# Shield_Moteur_DIP.net
KiCad netlist of a schematic drawn in EAGLE
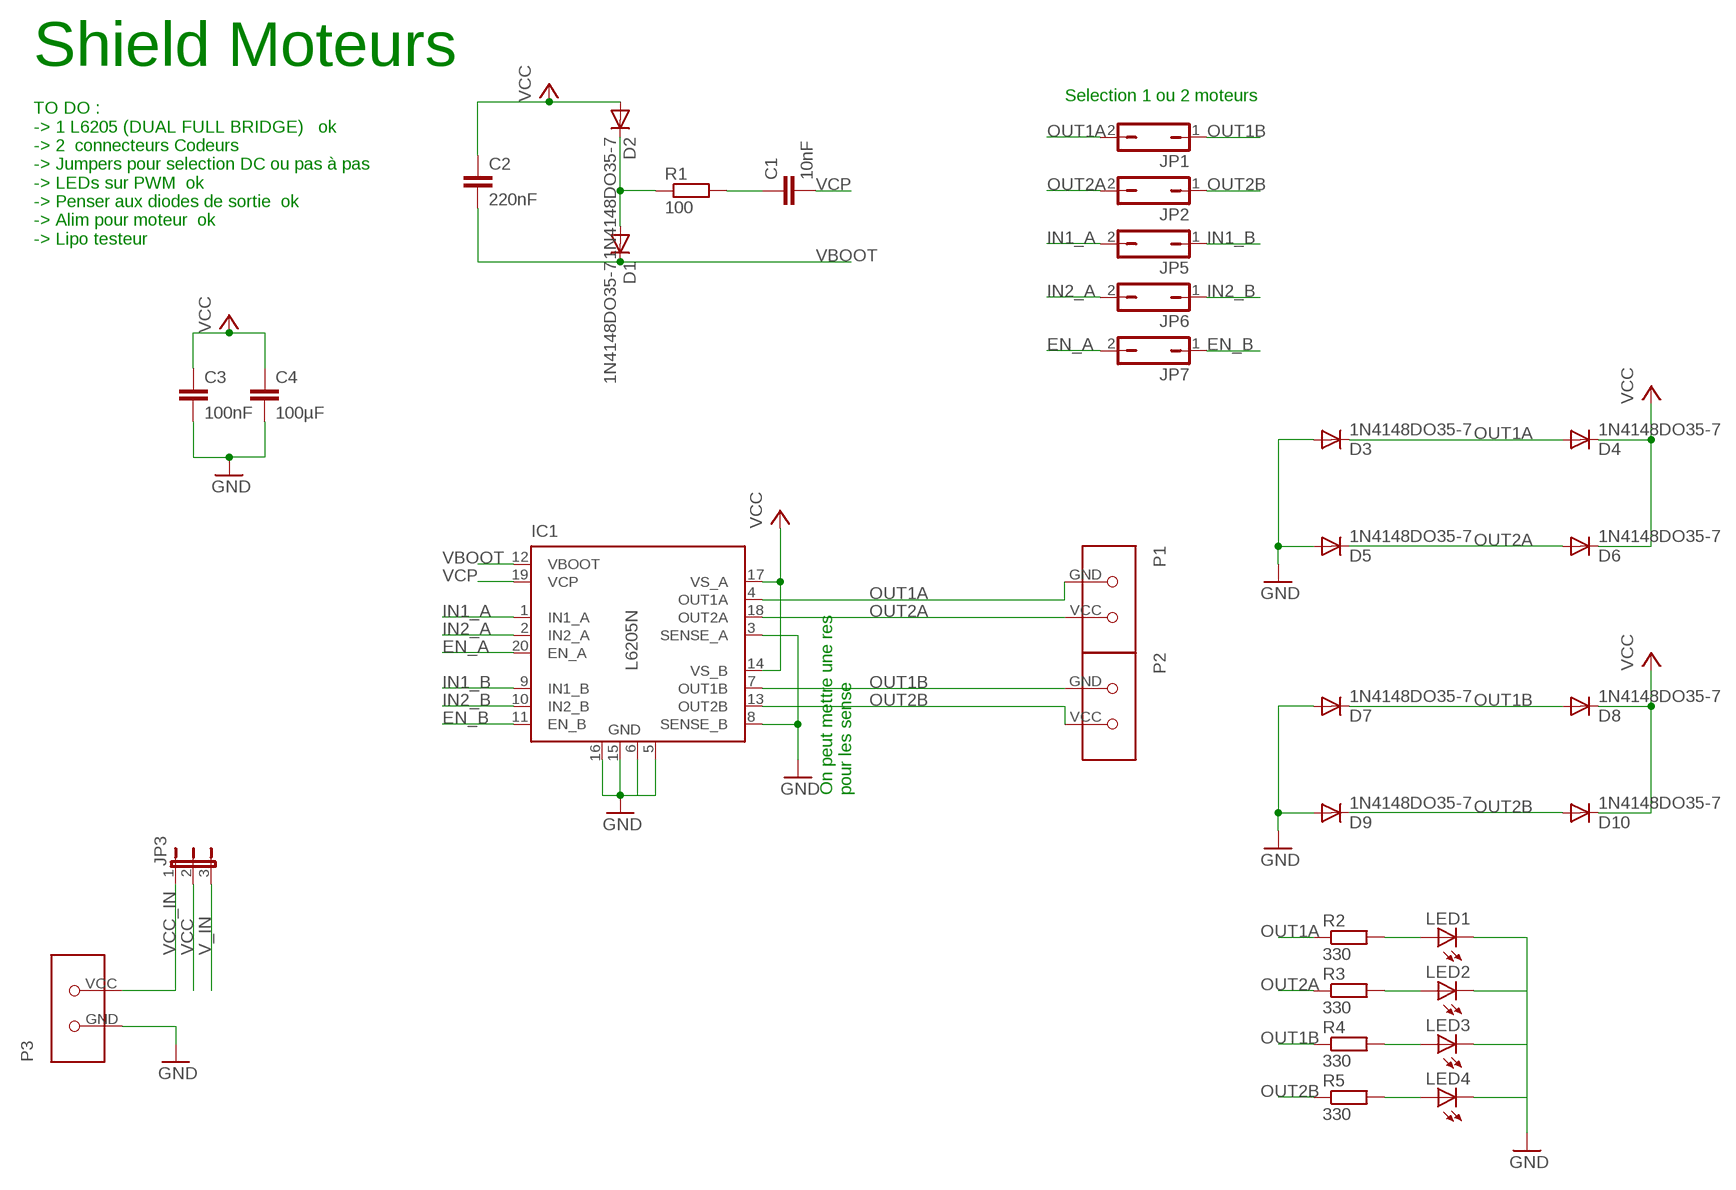
[diagram p0: schematic, sheet 1]

(export (version "E")
  (design (tool "Eeschema 10.0.6"))
  (components
    (comp (ref "C1")
      (value "10nF")
      (footprint "eagle-import:C050-035X075")
      (libsource (lib "eagle-import") (part "C-EU050-035X075"))
    )
    (comp (ref "C2")
      (value "220nF")
      (footprint "eagle-import:C050-035X075")
      (libsource (lib "eagle-import") (part "C-EU050-035X075"))
    )
    (comp (ref "C3")
      (value "100nF")
      (footprint "eagle-import:C050-035X075")
      (libsource (lib "eagle-import") (part "C-EU050-035X075"))
    )
    (comp (ref "C4")
      (value "100µF")
      (footprint "eagle-import:C050-035X075")
      (libsource (lib "eagle-import") (part "C-EU050-035X075"))
    )
    (comp (ref "D1")
      (value "1N4148DO35-7")
      (footprint "eagle-import:DO35-7")
      (libsource (lib "eagle-import") (part "1N4148DO35-7"))
    )
    (comp (ref "D2")
      (value "1N4148DO35-7")
      (footprint "eagle-import:DO35-7")
      (libsource (lib "eagle-import") (part "1N4148DO35-7"))
    )
    (comp (ref "D3")
      (value "1N4148DO35-7")
      (footprint "eagle-import:DO35-7")
      (libsource (lib "eagle-import") (part "1N4148DO35-7"))
    )
    (comp (ref "D4")
      (value "1N4148DO35-7")
      (footprint "eagle-import:DO35-7")
      (libsource (lib "eagle-import") (part "1N4148DO35-7"))
    )
    (comp (ref "D5")
      (value "1N4148DO35-7")
      (footprint "eagle-import:DO35-7")
      (libsource (lib "eagle-import") (part "1N4148DO35-7"))
    )
    (comp (ref "D6")
      (value "1N4148DO35-7")
      (footprint "eagle-import:DO35-7")
      (libsource (lib "eagle-import") (part "1N4148DO35-7"))
    )
    (comp (ref "D7")
      (value "1N4148DO35-7")
      (footprint "eagle-import:DO35-7")
      (libsource (lib "eagle-import") (part "1N4148DO35-7"))
    )
    (comp (ref "D8")
      (value "1N4148DO35-7")
      (footprint "eagle-import:DO35-7")
      (libsource (lib "eagle-import") (part "1N4148DO35-7"))
    )
    (comp (ref "D9")
      (value "1N4148DO35-7")
      (footprint "eagle-import:DO35-7")
      (libsource (lib "eagle-import") (part "1N4148DO35-7"))
    )
    (comp (ref "D10")
      (value "1N4148DO35-7")
      (footprint "eagle-import:DO35-7")
      (libsource (lib "eagle-import") (part "1N4148DO35-7"))
    )
    (comp (ref "IC1")
      (value "L6205N")
      (footprint "eagle-import:DIL20")
      (fields (field (name "MF") "Arrow Electronics"))
      (libsource (lib "eagle-import") (part "L6205N"))
    )
    (comp (ref "JP1")
      (value "JP1Q")
      (footprint "eagle-import:JP1")
      (libsource (lib "eagle-import") (part "JP1Q"))
    )
    (comp (ref "JP2")
      (value "JP1Q")
      (footprint "eagle-import:JP1")
      (libsource (lib "eagle-import") (part "JP1Q"))
    )
    (comp (ref "JP3")
      (value "JP2E")
      (footprint "eagle-import:JP2")
      (libsource (lib "eagle-import") (part "JP2E"))
    )
    (comp (ref "JP5")
      (value "JP1Q")
      (footprint "eagle-import:JP1")
      (libsource (lib "eagle-import") (part "JP1Q"))
    )
    (comp (ref "JP6")
      (value "JP1Q")
      (footprint "eagle-import:JP1")
      (libsource (lib "eagle-import") (part "JP1Q"))
    )
    (comp (ref "JP7")
      (value "JP1Q")
      (footprint "eagle-import:JP1")
      (libsource (lib "eagle-import") (part "JP1Q"))
    )
    (comp (ref "LED1")
      (value "LED3MM")
      (footprint "eagle-import:LED3MM")
      (libsource (lib "eagle-import") (part "LED3MM"))
    )
    (comp (ref "LED2")
      (value "LED3MM")
      (footprint "eagle-import:LED3MM")
      (libsource (lib "eagle-import") (part "LED3MM"))
    )
    (comp (ref "LED3")
      (value "LED3MM")
      (footprint "eagle-import:LED3MM")
      (libsource (lib "eagle-import") (part "LED3MM"))
    )
    (comp (ref "LED4")
      (value "LED3MM")
      (footprint "eagle-import:LED3MM")
      (libsource (lib "eagle-import") (part "LED3MM"))
    )
    (comp (ref "P1")
      (value "BORNIER_3.5MM")
      (footprint "eagle-import:BORNIER_COUDEE_3.5")
      (libsource (lib "eagle-import") (part "BORNIER_3.5MM"))
    )
    (comp (ref "P2")
      (value "BORNIER_3.5MM")
      (footprint "eagle-import:BORNIER_COUDEE_3.5")
      (libsource (lib "eagle-import") (part "BORNIER_3.5MM"))
    )
    (comp (ref "P3")
      (value "BORNIER_3.5MM")
      (footprint "eagle-import:BORNIER_COUDEE_3.5")
      (libsource (lib "eagle-import") (part "BORNIER_3.5MM"))
    )
    (comp (ref "R1")
      (value "100")
      (footprint "eagle-import:0204_7")
      (libsource (lib "eagle-import") (part "R-EU_0204/7"))
    )
    (comp (ref "R2")
      (value "330")
      (footprint "eagle-import:0204_7")
      (libsource (lib "eagle-import") (part "R-EU_0204/7"))
    )
    (comp (ref "R3")
      (value "330")
      (footprint "eagle-import:0204_7")
      (libsource (lib "eagle-import") (part "R-EU_0204/7"))
    )
    (comp (ref "R4")
      (value "330")
      (footprint "eagle-import:0204_7")
      (libsource (lib "eagle-import") (part "R-EU_0204/7"))
    )
    (comp (ref "R5")
      (value "330")
      (footprint "eagle-import:0204_7")
      (libsource (lib "eagle-import") (part "R-EU_0204/7"))
    )
  )
  (nets
    (net (code "1") (name "/EN_A") (class "Default")
      (node (ref "IC1") (pin "20") (pinfunction "EN_A_20") (pintype "input"))
      (node (ref "JP7") (pin "2") (pinfunction "2_2") (pintype "passive"))
    )
    (net (code "2") (name "/EN_B") (class "Default")
      (node (ref "IC1") (pin "11") (pinfunction "EN_B_11") (pintype "input"))
      (node (ref "JP7") (pin "1") (pinfunction "1_1") (pintype "passive"))
    )
    (net (code "3") (name "/IN1_A") (class "Default")
      (node (ref "IC1") (pin "1") (pinfunction "IN1_A_1") (pintype "input"))
      (node (ref "JP5") (pin "2") (pinfunction "2_2") (pintype "passive"))
    )
    (net (code "4") (name "/IN1_B") (class "Default")
      (node (ref "IC1") (pin "9") (pinfunction "IN1_B_9") (pintype "input"))
      (node (ref "JP5") (pin "1") (pinfunction "1_1") (pintype "passive"))
    )
    (net (code "5") (name "/IN2_A") (class "Default")
      (node (ref "IC1") (pin "2") (pinfunction "IN2_A_2") (pintype "input"))
      (node (ref "JP6") (pin "2") (pinfunction "2_2") (pintype "passive"))
    )
    (net (code "6") (name "/IN2_B") (class "Default")
      (node (ref "IC1") (pin "10") (pinfunction "IN2_B_10") (pintype "input"))
      (node (ref "JP6") (pin "1") (pinfunction "1_1") (pintype "passive"))
    )
    (net (code "7") (name "/OUT1A") (class "Default")
      (node (ref "D3") (pin "C") (pinfunction "C_C") (pintype "passive"))
      (node (ref "D4") (pin "A") (pinfunction "A_A") (pintype "passive"))
      (node (ref "IC1") (pin "4") (pinfunction "OUT1A_4") (pintype "output"))
      (node (ref "JP1") (pin "2") (pinfunction "2_2") (pintype "passive"))
      (node (ref "P1") (pin "GND") (pinfunction "GND_GND") (pintype "bidirectional"))
      (node (ref "R2") (pin "1") (pinfunction "1_1") (pintype "passive"))
    )
    (net (code "8") (name "/OUT1B") (class "Default")
      (node (ref "D7") (pin "C") (pinfunction "C_C") (pintype "passive"))
      (node (ref "D8") (pin "A") (pinfunction "A_A") (pintype "passive"))
      (node (ref "IC1") (pin "7") (pinfunction "OUT1B_7") (pintype "output"))
      (node (ref "JP1") (pin "1") (pinfunction "1_1") (pintype "passive"))
      (node (ref "P2") (pin "GND") (pinfunction "GND_GND") (pintype "bidirectional"))
      (node (ref "R4") (pin "1") (pinfunction "1_1") (pintype "passive"))
    )
    (net (code "9") (name "/OUT2A") (class "Default")
      (node (ref "D5") (pin "C") (pinfunction "C_C") (pintype "passive"))
      (node (ref "D6") (pin "A") (pinfunction "A_A") (pintype "passive"))
      (node (ref "IC1") (pin "18") (pinfunction "OUT2A_18") (pintype "output"))
      (node (ref "JP2") (pin "2") (pinfunction "2_2") (pintype "passive"))
      (node (ref "P1") (pin "VCC") (pinfunction "VCC_VCC") (pintype "bidirectional"))
      (node (ref "R3") (pin "1") (pinfunction "1_1") (pintype "passive"))
    )
    (net (code "10") (name "/OUT2B") (class "Default")
      (node (ref "D10") (pin "A") (pinfunction "A_A") (pintype "passive"))
      (node (ref "D9") (pin "C") (pinfunction "C_C") (pintype "passive"))
      (node (ref "IC1") (pin "13") (pinfunction "OUT2B_13") (pintype "output"))
      (node (ref "JP2") (pin "1") (pinfunction "1_1") (pintype "passive"))
      (node (ref "P2") (pin "VCC") (pinfunction "VCC_VCC") (pintype "bidirectional"))
      (node (ref "R5") (pin "1") (pinfunction "1_1") (pintype "passive"))
    )
    (net (code "11") (name "/VBOOT") (class "Default")
      (node (ref "C2") (pin "2") (pinfunction "2_2") (pintype "passive"))
      (node (ref "D1") (pin "C") (pinfunction "C_C") (pintype "passive"))
      (node (ref "IC1") (pin "12") (pinfunction "VBOOT_12") (pintype "power_in"))
    )
    (net (code "12") (name "/VCC_IN") (class "Default")
      (node (ref "JP3") (pin "1") (pinfunction "1_1") (pintype "passive"))
      (node (ref "P3") (pin "VCC") (pinfunction "VCC_VCC") (pintype "bidirectional"))
    )
    (net (code "13") (name "/VCP") (class "Default")
      (node (ref "C1") (pin "2") (pinfunction "2_2") (pintype "passive"))
      (node (ref "IC1") (pin "19") (pinfunction "VCP_19") (pintype "power_in"))
    )
    (net (code "14") (name "/V_IN") (class "Default")
      (node (ref "JP3") (pin "3") (pinfunction "3_3") (pintype "passive"))
    )
    (net (code "15") (name "GND") (class "Default")
      (node (ref "C3") (pin "2") (pinfunction "2_2") (pintype "passive"))
      (node (ref "C4") (pin "2") (pinfunction "2_2") (pintype "passive"))
      (node (ref "D3") (pin "A") (pinfunction "A_A") (pintype "passive"))
      (node (ref "D5") (pin "A") (pinfunction "A_A") (pintype "passive"))
      (node (ref "D7") (pin "A") (pinfunction "A_A") (pintype "passive"))
      (node (ref "D9") (pin "A") (pinfunction "A_A") (pintype "passive"))
      (node (ref "IC1") (pin "15") (pinfunction "GND_15") (pintype "power_in"))
      (node (ref "IC1") (pin "16") (pinfunction "GND_16") (pintype "power_in"))
      (node (ref "IC1") (pin "3") (pinfunction "SENSE_A_3") (pintype "input"))
      (node (ref "IC1") (pin "5") (pinfunction "GND_5") (pintype "power_in"))
      (node (ref "IC1") (pin "6") (pinfunction "GND_6") (pintype "power_in"))
      (node (ref "IC1") (pin "8") (pinfunction "SENSE_B_8") (pintype "input"))
      (node (ref "LED1") (pin "K") (pinfunction "C_K") (pintype "passive"))
      (node (ref "LED2") (pin "K") (pinfunction "C_K") (pintype "passive"))
      (node (ref "LED3") (pin "K") (pinfunction "C_K") (pintype "passive"))
      (node (ref "LED4") (pin "K") (pinfunction "C_K") (pintype "passive"))
      (node (ref "P3") (pin "GND") (pinfunction "GND_GND") (pintype "bidirectional"))
    )
    (net (code "16") (name "Net-(C1-Pad1)") (class "Default")
      (node (ref "C1") (pin "1") (pinfunction "1_1") (pintype "passive"))
      (node (ref "R1") (pin "2") (pinfunction "2_2") (pintype "passive"))
    )
    (net (code "17") (name "Net-(D1-PadA)") (class "Default")
      (node (ref "D1") (pin "A") (pinfunction "A_A") (pintype "passive"))
      (node (ref "D2") (pin "C") (pinfunction "C_C") (pintype "passive"))
      (node (ref "R1") (pin "1") (pinfunction "1_1") (pintype "passive"))
    )
    (net (code "18") (name "Net-(LED1-PadA)") (class "Default")
      (node (ref "LED1") (pin "A") (pinfunction "A_A") (pintype "passive"))
      (node (ref "R2") (pin "2") (pinfunction "2_2") (pintype "passive"))
    )
    (net (code "19") (name "Net-(LED2-PadA)") (class "Default")
      (node (ref "LED2") (pin "A") (pinfunction "A_A") (pintype "passive"))
      (node (ref "R3") (pin "2") (pinfunction "2_2") (pintype "passive"))
    )
    (net (code "20") (name "Net-(LED3-PadA)") (class "Default")
      (node (ref "LED3") (pin "A") (pinfunction "A_A") (pintype "passive"))
      (node (ref "R4") (pin "2") (pinfunction "2_2") (pintype "passive"))
    )
    (net (code "21") (name "Net-(LED4-PadA)") (class "Default")
      (node (ref "LED4") (pin "A") (pinfunction "A_A") (pintype "passive"))
      (node (ref "R5") (pin "2") (pinfunction "2_2") (pintype "passive"))
    )
    (net (code "22") (name "VCC") (class "Default")
      (node (ref "C2") (pin "1") (pinfunction "1_1") (pintype "passive"))
      (node (ref "C3") (pin "1") (pinfunction "1_1") (pintype "passive"))
      (node (ref "C4") (pin "1") (pinfunction "1_1") (pintype "passive"))
      (node (ref "D10") (pin "C") (pinfunction "C_C") (pintype "passive"))
      (node (ref "D2") (pin "A") (pinfunction "A_A") (pintype "passive"))
      (node (ref "D4") (pin "C") (pinfunction "C_C") (pintype "passive"))
      (node (ref "D6") (pin "C") (pinfunction "C_C") (pintype "passive"))
      (node (ref "D8") (pin "C") (pinfunction "C_C") (pintype "passive"))
      (node (ref "IC1") (pin "14") (pinfunction "VS_B_14") (pintype "power_in"))
      (node (ref "IC1") (pin "17") (pinfunction "VS_A_17") (pintype "power_in"))
      (node (ref "JP3") (pin "2") (pinfunction "2_2") (pintype "passive"))
    )
  )
)
